# CDH-v4_11-A-DS1338-tcc-test-redesign.net
KiCad netlist of a schematic drawn in EAGLE
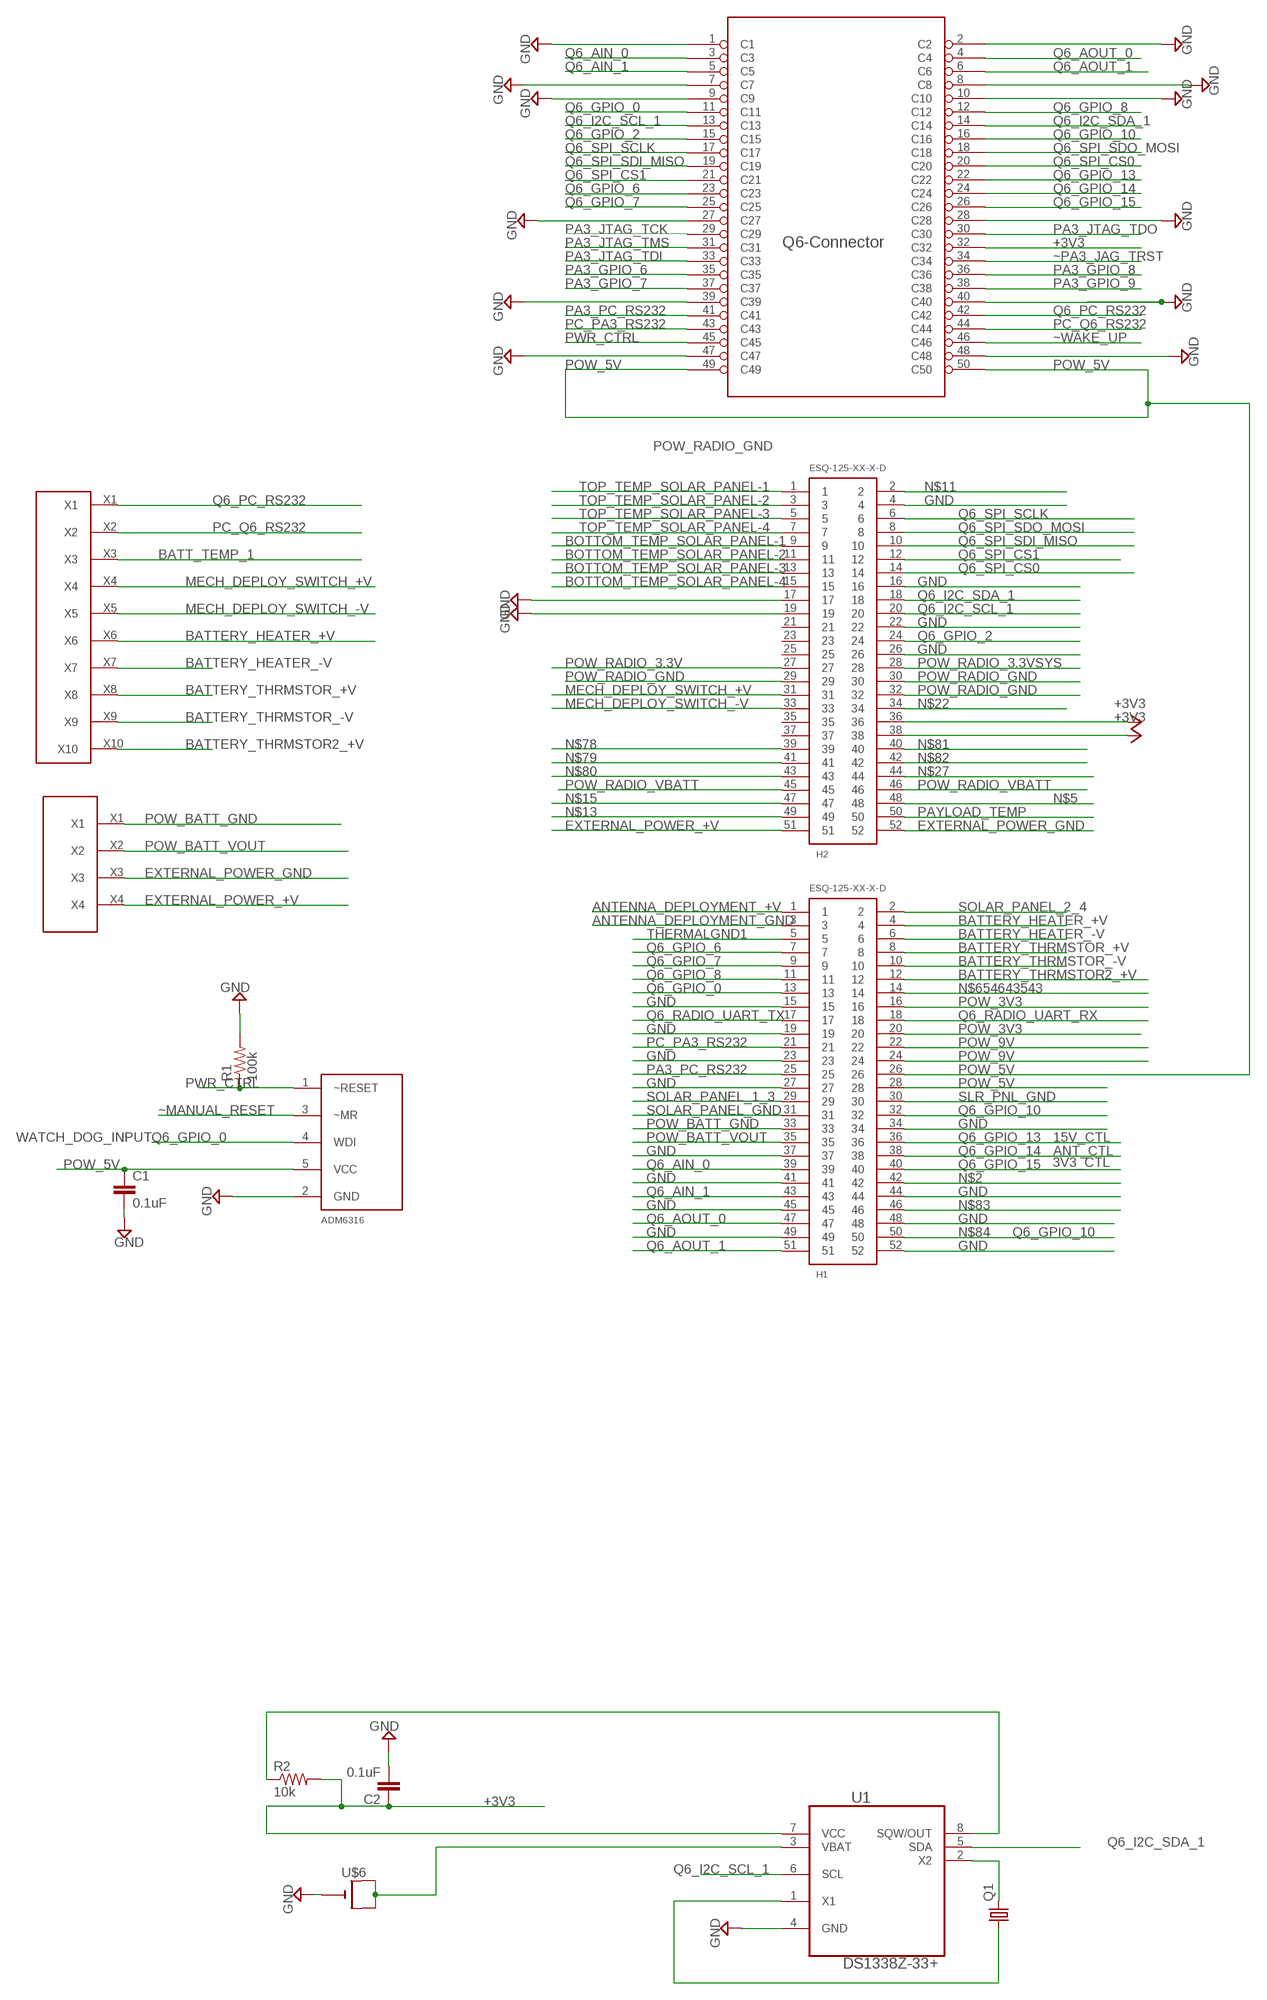
[diagram p0: schematic, sheet 1, part 1 of 2]
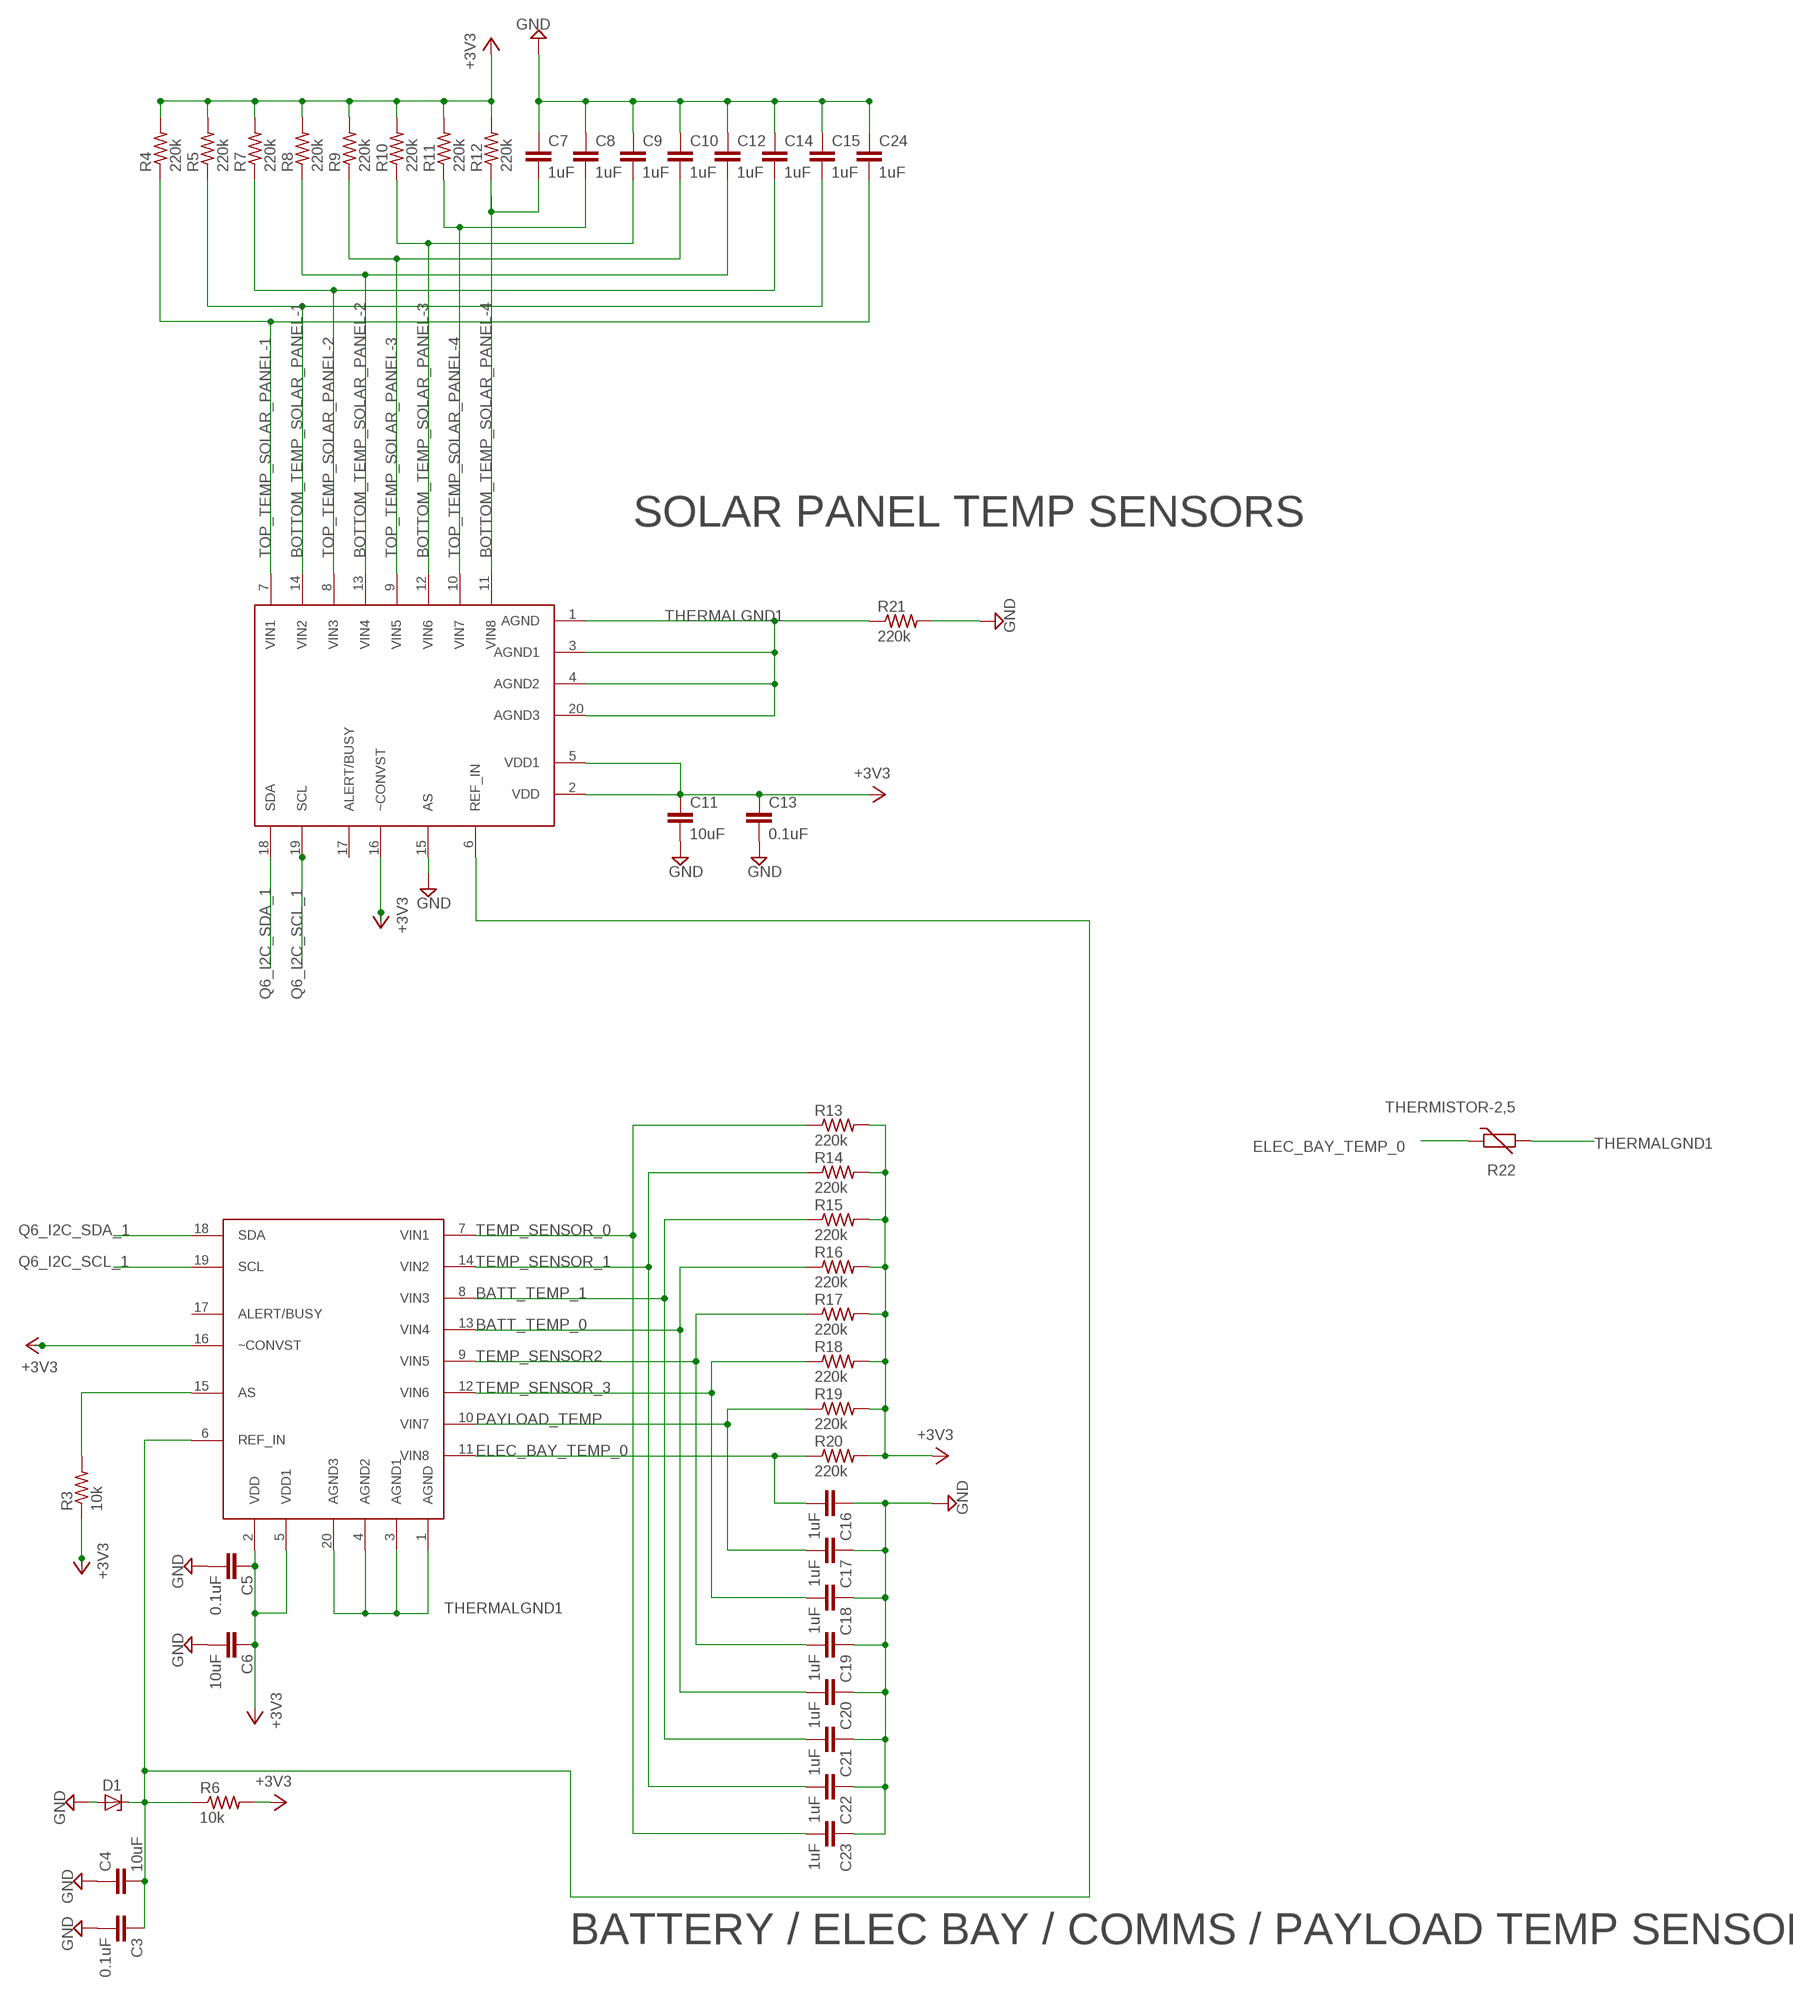
[diagram p1: schematic, sheet 1, part 2 of 2]

(export (version "E")
  (design (tool "Eeschema 10.0.6"))
  (components
    (comp (ref "ADC_TEMP_1")
      (value "AD7998-1")
      (footprint "eagle-import:TSSOP20")
      (libsource (lib "eagle-import") (part "AD7998-1"))
    )
    (comp (ref "ADC_TEMP_2")
      (value "AD7998-1")
      (footprint "eagle-import:TSSOP20")
      (libsource (lib "eagle-import") (part "AD7998-1"))
    )
    (comp (ref "C1")
      (value "0.1uF")
      (footprint "eagle-import:C2012")
      (libsource (lib "eagle-import") (part "C-EUC2012"))
    )
    (comp (ref "C2")
      (value "0.1uF")
      (footprint "eagle-import:C2012")
      (libsource (lib "eagle-import") (part "C-EUC2012"))
    )
    (comp (ref "C3")
      (value "0.1uF")
      (footprint "eagle-import:C2012")
      (libsource (lib "eagle-import") (part "C-EUC2012"))
    )
    (comp (ref "C4")
      (value "10uF")
      (footprint "eagle-import:C2012")
      (libsource (lib "eagle-import") (part "C-EUC2012"))
    )
    (comp (ref "C5")
      (value "0.1uF")
      (footprint "eagle-import:C2012")
      (libsource (lib "eagle-import") (part "C-EUC2012"))
    )
    (comp (ref "C6")
      (value "10uF")
      (footprint "eagle-import:C2012")
      (libsource (lib "eagle-import") (part "C-EUC2012"))
    )
    (comp (ref "C7")
      (value "1uF")
      (footprint "eagle-import:C2012")
      (libsource (lib "eagle-import") (part "C-EUC2012"))
    )
    (comp (ref "C8")
      (value "1uF")
      (footprint "eagle-import:C2012")
      (libsource (lib "eagle-import") (part "C-EUC2012"))
    )
    (comp (ref "C9")
      (value "1uF")
      (footprint "eagle-import:C2012")
      (libsource (lib "eagle-import") (part "C-EUC2012"))
    )
    (comp (ref "C10")
      (value "1uF")
      (footprint "eagle-import:C2012")
      (libsource (lib "eagle-import") (part "C-EUC2012"))
    )
    (comp (ref "C11")
      (value "10uF")
      (footprint "eagle-import:C2012")
      (libsource (lib "eagle-import") (part "C-EUC2012"))
    )
    (comp (ref "C12")
      (value "1uF")
      (footprint "eagle-import:C2012")
      (libsource (lib "eagle-import") (part "C-EUC2012"))
    )
    (comp (ref "C13")
      (value "0.1uF")
      (footprint "eagle-import:C2012")
      (libsource (lib "eagle-import") (part "C-EUC2012"))
    )
    (comp (ref "C14")
      (value "1uF")
      (footprint "eagle-import:C2012")
      (libsource (lib "eagle-import") (part "C-EUC2012"))
    )
    (comp (ref "C15")
      (value "1uF")
      (footprint "eagle-import:C2012")
      (libsource (lib "eagle-import") (part "C-EUC2012"))
    )
    (comp (ref "C16")
      (value "1uF")
      (footprint "eagle-import:C2012")
      (libsource (lib "eagle-import") (part "C-EUC2012"))
    )
    (comp (ref "C17")
      (value "1uF")
      (footprint "eagle-import:C2012")
      (libsource (lib "eagle-import") (part "C-EUC2012"))
    )
    (comp (ref "C18")
      (value "1uF")
      (footprint "eagle-import:C2012")
      (libsource (lib "eagle-import") (part "C-EUC2012"))
    )
    (comp (ref "C19")
      (value "1uF")
      (footprint "eagle-import:C2012")
      (libsource (lib "eagle-import") (part "C-EUC2012"))
    )
    (comp (ref "C20")
      (value "1uF")
      (footprint "eagle-import:C2012")
      (libsource (lib "eagle-import") (part "C-EUC2012"))
    )
    (comp (ref "C21")
      (value "1uF")
      (footprint "eagle-import:C2012")
      (libsource (lib "eagle-import") (part "C-EUC2012"))
    )
    (comp (ref "C22")
      (value "1uF")
      (footprint "eagle-import:C2012")
      (libsource (lib "eagle-import") (part "C-EUC2012"))
    )
    (comp (ref "C23")
      (value "1uF")
      (footprint "eagle-import:C2012")
      (libsource (lib "eagle-import") (part "C-EUC2012"))
    )
    (comp (ref "C24")
      (value "1uF")
      (footprint "eagle-import:C2012")
      (libsource (lib "eagle-import") (part "C-EUC2012"))
    )
    (comp (ref "D1")
      (value "ZENER-DIODESOD80C")
      (footprint "eagle-import:SOD80C")
      (libsource (lib "eagle-import") (part "ZENER-DIODESOD80C"))
    )
    (comp (ref "H1")
      (value "ESQ-125-XX-X-D")
      (footprint "eagle-import:ESQ-125-XX-X-D")
      (libsource (lib "eagle-import") (part "ESQ-125-XX-X-D"))
    )
    (comp (ref "H2")
      (value "ESQ-125-XX-X-D")
      (footprint "eagle-import:ESQ-125-XX-X-D")
      (libsource (lib "eagle-import") (part "ESQ-125-XX-X-D"))
    )
    (comp (ref "Q1")
      (value "CRYSTALTC38H")
      (footprint "eagle-import:TC38H")
      (libsource (lib "eagle-import") (part "CRYSTALTC38H"))
    )
    (comp (ref "R1")
      (value "100k")
      (footprint "eagle-import:R2012")
      (libsource (lib "eagle-import") (part "R-US_R2012"))
    )
    (comp (ref "R2")
      (value "10k")
      (footprint "eagle-import:R2012")
      (libsource (lib "eagle-import") (part "R-US_R2012"))
    )
    (comp (ref "R3")
      (value "10k")
      (footprint "eagle-import:R2012")
      (libsource (lib "eagle-import") (part "R-US_R2012"))
    )
    (comp (ref "R4")
      (value "220k")
      (footprint "eagle-import:R2012")
      (libsource (lib "eagle-import") (part "R-US_R2012"))
    )
    (comp (ref "R5")
      (value "220k")
      (footprint "eagle-import:R2012")
      (libsource (lib "eagle-import") (part "R-US_R2012"))
    )
    (comp (ref "R6")
      (value "10k")
      (footprint "eagle-import:R2012")
      (libsource (lib "eagle-import") (part "R-US_R2012"))
    )
    (comp (ref "R7")
      (value "220k")
      (footprint "eagle-import:R2012")
      (libsource (lib "eagle-import") (part "R-US_R2012"))
    )
    (comp (ref "R8")
      (value "220k")
      (footprint "eagle-import:R2012")
      (libsource (lib "eagle-import") (part "R-US_R2012"))
    )
    (comp (ref "R9")
      (value "220k")
      (footprint "eagle-import:R2012")
      (libsource (lib "eagle-import") (part "R-US_R2012"))
    )
    (comp (ref "R10")
      (value "220k")
      (footprint "eagle-import:R2012")
      (libsource (lib "eagle-import") (part "R-US_R2012"))
    )
    (comp (ref "R11")
      (value "220k")
      (footprint "eagle-import:R2012")
      (libsource (lib "eagle-import") (part "R-US_R2012"))
    )
    (comp (ref "R12")
      (value "220k")
      (footprint "eagle-import:R2012")
      (libsource (lib "eagle-import") (part "R-US_R2012"))
    )
    (comp (ref "R13")
      (value "220k")
      (footprint "eagle-import:R2012")
      (libsource (lib "eagle-import") (part "R-US_R2012"))
    )
    (comp (ref "R14")
      (value "220k")
      (footprint "eagle-import:R2012")
      (libsource (lib "eagle-import") (part "R-US_R2012"))
    )
    (comp (ref "R15")
      (value "220k")
      (footprint "eagle-import:R2012")
      (libsource (lib "eagle-import") (part "R-US_R2012"))
    )
    (comp (ref "R16")
      (value "220k")
      (footprint "eagle-import:R2012")
      (libsource (lib "eagle-import") (part "R-US_R2012"))
    )
    (comp (ref "R17")
      (value "220k")
      (footprint "eagle-import:R2012")
      (libsource (lib "eagle-import") (part "R-US_R2012"))
    )
    (comp (ref "R18")
      (value "220k")
      (footprint "eagle-import:R2012")
      (libsource (lib "eagle-import") (part "R-US_R2012"))
    )
    (comp (ref "R19")
      (value "220k")
      (footprint "eagle-import:R2012")
      (libsource (lib "eagle-import") (part "R-US_R2012"))
    )
    (comp (ref "R20")
      (value "220k")
      (footprint "eagle-import:R2012")
      (libsource (lib "eagle-import") (part "R-US_R2012"))
    )
    (comp (ref "R21")
      (value "220k")
      (footprint "eagle-import:R2012")
      (libsource (lib "eagle-import") (part "R-US_R2012"))
    )
    (comp (ref "R22")
      (value "THERMISTOR-2,5")
      (footprint "eagle-import:RS-2,5")
      (libsource (lib "eagle-import") (part "THERMISTOR-2,5"))
    )
    (comp (ref "U$1")
      (value "M80-5000000M1-10-331-00-000")
      (footprint "eagle-import:M80-5000000M1-04-331-00-000")
      (libsource (lib "eagle-import") (part "M80-5000000M1-10-331-00-000"))
    )
    (comp (ref "U$2")
      (value "M80-5000000M1-10-331-000")
      (footprint "eagle-import:M80-5000000M1")
      (libsource (lib "eagle-import") (part "M80-5000000M1-10-331-000"))
    )
    (comp (ref "U$3")
      (value "ADM6316/ADM6320")
      (footprint "eagle-import:SOT23-5")
      (libsource (lib "eagle-import") (part "ADM6316/ADM6320"))
    )
    (comp (ref "U$4")
      (value "SMFC")
      (footprint "eagle-import:SFMC-107-01-XX-D")
      (libsource (lib "eagle-import") (part "SMFC"))
    )
    (comp (ref "U$6")
      (value "CR1220SMT")
      (footprint "eagle-import:CR1220-SMD")
      (libsource (lib "eagle-import") (part "CR1220SMT"))
    )
    (comp (ref "U1")
      (value "DS1338Z-33+")
      (footprint "eagle-import:SOIC127P600X175-8N")
      (libsource (lib "eagle-import") (part "DS1338Z-33+"))
    )
  )
  (nets
    (net (code "1") (name "+3V3") (class "Default")
      (node (ref "ADC_TEMP_1") (pin "16") (pinfunction "~{CONVST}_16") (pintype "bidirectional"))
      (node (ref "ADC_TEMP_1") (pin "2") (pinfunction "VDD_2") (pintype "bidirectional"))
      (node (ref "ADC_TEMP_1") (pin "5") (pinfunction "VDD1_5") (pintype "bidirectional"))
      (node (ref "ADC_TEMP_2") (pin "16") (pinfunction "~{CONVST}_16") (pintype "bidirectional"))
      (node (ref "ADC_TEMP_2") (pin "2") (pinfunction "VDD_2") (pintype "bidirectional"))
      (node (ref "ADC_TEMP_2") (pin "5") (pinfunction "VDD1_5") (pintype "bidirectional"))
      (node (ref "C11") (pin "1") (pinfunction "1_1") (pintype "passive"))
      (node (ref "C13") (pin "1") (pinfunction "1_1") (pintype "passive"))
      (node (ref "C2") (pin "1") (pinfunction "1_1") (pintype "passive"))
      (node (ref "C5") (pin "1") (pinfunction "1_1") (pintype "passive"))
      (node (ref "C6") (pin "1") (pinfunction "1_1") (pintype "passive"))
      (node (ref "H2") (pin "36") (pinfunction "36_36") (pintype "bidirectional"))
      (node (ref "H2") (pin "38") (pinfunction "38_38") (pintype "bidirectional"))
      (node (ref "R10") (pin "2") (pinfunction "2_2") (pintype "passive"))
      (node (ref "R11") (pin "2") (pinfunction "2_2") (pintype "passive"))
      (node (ref "R12") (pin "2") (pinfunction "2_2") (pintype "passive"))
      (node (ref "R13") (pin "2") (pinfunction "2_2") (pintype "passive"))
      (node (ref "R14") (pin "2") (pinfunction "2_2") (pintype "passive"))
      (node (ref "R15") (pin "2") (pinfunction "2_2") (pintype "passive"))
      (node (ref "R16") (pin "2") (pinfunction "2_2") (pintype "passive"))
      (node (ref "R17") (pin "2") (pinfunction "2_2") (pintype "passive"))
      (node (ref "R18") (pin "2") (pinfunction "2_2") (pintype "passive"))
      (node (ref "R19") (pin "2") (pinfunction "2_2") (pintype "passive"))
      (node (ref "R2") (pin "2") (pinfunction "2_2") (pintype "passive"))
      (node (ref "R20") (pin "2") (pinfunction "2_2") (pintype "passive"))
      (node (ref "R3") (pin "1") (pinfunction "1_1") (pintype "passive"))
      (node (ref "R4") (pin "2") (pinfunction "2_2") (pintype "passive"))
      (node (ref "R5") (pin "2") (pinfunction "2_2") (pintype "passive"))
      (node (ref "R6") (pin "2") (pinfunction "2_2") (pintype "passive"))
      (node (ref "R7") (pin "2") (pinfunction "2_2") (pintype "passive"))
      (node (ref "R8") (pin "2") (pinfunction "2_2") (pintype "passive"))
      (node (ref "R9") (pin "2") (pinfunction "2_2") (pintype "passive"))
      (node (ref "U$4") (pin "32") (pinfunction "C32_32") (pintype "bidirectional"))
      (node (ref "U1") (pin "7") (pinfunction "VCC_7") (pintype "power_in"))
    )
    (net (code "2") (name "/ANTENNA_DEPLOYMENT_+V") (class "Default")
      (node (ref "H1") (pin "1") (pinfunction "1_1") (pintype "bidirectional"))
    )
    (net (code "3") (name "/ANTENNA_DEPLOYMENT_GND") (class "Default")
      (node (ref "H1") (pin "3") (pinfunction "3_3") (pintype "bidirectional"))
    )
    (net (code "4") (name "/BATTERY_HEATER_+V") (class "Default")
      (node (ref "H1") (pin "4") (pinfunction "4_4") (pintype "bidirectional"))
      (node (ref "U$2") (pin "X6") (pinfunction "X6_X6") (pintype "bidirectional"))
    )
    (net (code "5") (name "/BATTERY_HEATER_-V") (class "Default")
      (node (ref "H1") (pin "6") (pinfunction "6_6") (pintype "bidirectional"))
      (node (ref "U$2") (pin "X7") (pinfunction "X7_X7") (pintype "bidirectional"))
    )
    (net (code "6") (name "/BATTERY_THRMSTOR2_+V") (class "Default")
      (node (ref "H1") (pin "12") (pinfunction "12_12") (pintype "bidirectional"))
      (node (ref "U$2") (pin "X10") (pinfunction "X10_X10") (pintype "bidirectional"))
    )
    (net (code "7") (name "/BATTERY_THRMSTOR_+V") (class "Default")
      (node (ref "H1") (pin "8") (pinfunction "8_8") (pintype "bidirectional"))
      (node (ref "U$2") (pin "X8") (pinfunction "X8_X8") (pintype "bidirectional"))
    )
    (net (code "8") (name "/BATTERY_THRMSTOR_-V") (class "Default")
      (node (ref "H1") (pin "10") (pinfunction "10_10") (pintype "bidirectional"))
      (node (ref "U$2") (pin "X9") (pinfunction "X9_X9") (pintype "bidirectional"))
    )
    (net (code "9") (name "/BATT_TEMP_0") (class "Default")
      (node (ref "ADC_TEMP_1") (pin "13") (pinfunction "VIN4_13") (pintype "bidirectional"))
      (node (ref "C20") (pin "2") (pinfunction "2_2") (pintype "passive"))
      (node (ref "R16") (pin "1") (pinfunction "1_1") (pintype "passive"))
    )
    (net (code "10") (name "/BATT_TEMP_1") (class "Default")
      (node (ref "ADC_TEMP_1") (pin "8") (pinfunction "VIN3_8") (pintype "bidirectional"))
      (node (ref "C21") (pin "2") (pinfunction "2_2") (pintype "passive"))
      (node (ref "R15") (pin "1") (pinfunction "1_1") (pintype "passive"))
      (node (ref "U$2") (pin "X3") (pinfunction "X3_X3") (pintype "bidirectional"))
    )
    (net (code "11") (name "/BOTTOM_TEMP_SOLAR_PANEL-1") (class "Default")
      (node (ref "ADC_TEMP_2") (pin "14") (pinfunction "VIN2_14") (pintype "bidirectional"))
      (node (ref "C15") (pin "2") (pinfunction "2_2") (pintype "passive"))
      (node (ref "H2") (pin "9") (pinfunction "9_9") (pintype "bidirectional"))
      (node (ref "R5") (pin "1") (pinfunction "1_1") (pintype "passive"))
    )
    (net (code "12") (name "/BOTTOM_TEMP_SOLAR_PANEL-2") (class "Default")
      (node (ref "ADC_TEMP_2") (pin "13") (pinfunction "VIN4_13") (pintype "bidirectional"))
      (node (ref "C12") (pin "2") (pinfunction "2_2") (pintype "passive"))
      (node (ref "H2") (pin "11") (pinfunction "11_11") (pintype "bidirectional"))
      (node (ref "R8") (pin "1") (pinfunction "1_1") (pintype "passive"))
    )
    (net (code "13") (name "/BOTTOM_TEMP_SOLAR_PANEL-3") (class "Default")
      (node (ref "ADC_TEMP_2") (pin "12") (pinfunction "VIN6_12") (pintype "bidirectional"))
      (node (ref "C9") (pin "2") (pinfunction "2_2") (pintype "passive"))
      (node (ref "H2") (pin "13") (pinfunction "13_13") (pintype "bidirectional"))
      (node (ref "R10") (pin "1") (pinfunction "1_1") (pintype "passive"))
    )
    (net (code "14") (name "/BOTTOM_TEMP_SOLAR_PANEL-4") (class "Default")
      (node (ref "ADC_TEMP_2") (pin "11") (pinfunction "VIN8_11") (pintype "bidirectional"))
      (node (ref "C7") (pin "2") (pinfunction "2_2") (pintype "passive"))
      (node (ref "H2") (pin "15") (pinfunction "15_15") (pintype "bidirectional"))
      (node (ref "R12") (pin "1") (pinfunction "1_1") (pintype "passive"))
    )
    (net (code "15") (name "/ELEC_BAY_TEMP_0") (class "Default")
      (node (ref "ADC_TEMP_1") (pin "11") (pinfunction "VIN8_11") (pintype "bidirectional"))
      (node (ref "C16") (pin "2") (pinfunction "2_2") (pintype "passive"))
      (node (ref "R20") (pin "1") (pinfunction "1_1") (pintype "passive"))
      (node (ref "R22") (pin "1") (pinfunction "1_1") (pintype "passive"))
    )
    (net (code "16") (name "/EXTERNAL_POWER_+V") (class "Default")
      (node (ref "H2") (pin "51") (pinfunction "51_51") (pintype "bidirectional"))
      (node (ref "U$1") (pin "X4") (pinfunction "X4_X4") (pintype "bidirectional"))
    )
    (net (code "17") (name "/EXTERNAL_POWER_GND") (class "Default")
      (node (ref "H2") (pin "52") (pinfunction "52_52") (pintype "bidirectional"))
      (node (ref "U$1") (pin "X3") (pinfunction "X3_X3") (pintype "bidirectional"))
    )
    (net (code "18") (name "/MECH_DEPLOY_SWITCH_+V") (class "Default")
      (node (ref "H2") (pin "31") (pinfunction "31_31") (pintype "bidirectional"))
      (node (ref "U$2") (pin "X4") (pinfunction "X4_X4") (pintype "bidirectional"))
    )
    (net (code "19") (name "/MECH_DEPLOY_SWITCH_-V") (class "Default")
      (node (ref "H2") (pin "33") (pinfunction "33_33") (pintype "bidirectional"))
      (node (ref "U$2") (pin "X5") (pinfunction "X5_X5") (pintype "bidirectional"))
    )
    (net (code "20") (name "/N$2") (class "Default")
      (node (ref "H1") (pin "42") (pinfunction "42_42") (pintype "bidirectional"))
    )
    (net (code "21") (name "/N$5") (class "Default")
      (node (ref "H2") (pin "48") (pinfunction "48_48") (pintype "bidirectional"))
    )
    (net (code "22") (name "/N$11") (class "Default")
      (node (ref "H2") (pin "2") (pinfunction "2_2") (pintype "bidirectional"))
    )
    (net (code "23") (name "/N$13") (class "Default")
      (node (ref "H2") (pin "49") (pinfunction "49_49") (pintype "bidirectional"))
    )
    (net (code "24") (name "/N$15") (class "Default")
      (node (ref "H2") (pin "47") (pinfunction "47_47") (pintype "bidirectional"))
    )
    (net (code "25") (name "/N$22") (class "Default")
      (node (ref "H2") (pin "34") (pinfunction "34_34") (pintype "bidirectional"))
    )
    (net (code "26") (name "/N$27") (class "Default")
      (node (ref "H2") (pin "44") (pinfunction "44_44") (pintype "bidirectional"))
    )
    (net (code "27") (name "/N$78") (class "Default")
      (node (ref "H2") (pin "39") (pinfunction "39_39") (pintype "bidirectional"))
    )
    (net (code "28") (name "/N$79") (class "Default")
      (node (ref "H2") (pin "41") (pinfunction "41_41") (pintype "bidirectional"))
    )
    (net (code "29") (name "/N$80") (class "Default")
      (node (ref "H2") (pin "43") (pinfunction "43_43") (pintype "bidirectional"))
    )
    (net (code "30") (name "/N$81") (class "Default")
      (node (ref "H2") (pin "40") (pinfunction "40_40") (pintype "bidirectional"))
    )
    (net (code "31") (name "/N$82") (class "Default")
      (node (ref "H2") (pin "42") (pinfunction "42_42") (pintype "bidirectional"))
    )
    (net (code "32") (name "/N$83") (class "Default")
      (node (ref "H1") (pin "46") (pinfunction "46_46") (pintype "bidirectional"))
    )
    (net (code "33") (name "/N$84") (class "Default")
      (node (ref "H1") (pin "50") (pinfunction "50_50") (pintype "bidirectional"))
    )
    (net (code "34") (name "/N$654643543") (class "Default")
      (node (ref "H1") (pin "14") (pinfunction "14_14") (pintype "bidirectional"))
    )
    (net (code "35") (name "/PA3_GPIO_6") (class "Default")
      (node (ref "U$4") (pin "35") (pinfunction "C35_35") (pintype "bidirectional"))
    )
    (net (code "36") (name "/PA3_GPIO_7") (class "Default")
      (node (ref "U$4") (pin "37") (pinfunction "C37_37") (pintype "bidirectional"))
    )
    (net (code "37") (name "/PA3_GPIO_8") (class "Default")
      (node (ref "U$4") (pin "36") (pinfunction "C36_36") (pintype "bidirectional"))
    )
    (net (code "38") (name "/PA3_GPIO_9") (class "Default")
      (node (ref "U$4") (pin "38") (pinfunction "C38_38") (pintype "bidirectional"))
    )
    (net (code "39") (name "/PA3_JTAG_TCK") (class "Default")
      (node (ref "U$4") (pin "29") (pinfunction "C29_29") (pintype "bidirectional"))
    )
    (net (code "40") (name "/PA3_JTAG_TDI") (class "Default")
      (node (ref "U$4") (pin "33") (pinfunction "C33_33") (pintype "bidirectional"))
    )
    (net (code "41") (name "/PA3_JTAG_TDO") (class "Default")
      (node (ref "U$4") (pin "30") (pinfunction "C30_30") (pintype "bidirectional"))
    )
    (net (code "42") (name "/PA3_JTAG_TMS") (class "Default")
      (node (ref "U$4") (pin "31") (pinfunction "C31_31") (pintype "bidirectional"))
    )
    (net (code "43") (name "/PA3_PC_RS232") (class "Default")
      (node (ref "H1") (pin "25") (pinfunction "25_25") (pintype "bidirectional"))
      (node (ref "U$4") (pin "41") (pinfunction "C41_41") (pintype "bidirectional"))
    )
    (net (code "44") (name "/PAYLOAD_TEMP") (class "Default")
      (node (ref "ADC_TEMP_1") (pin "10") (pinfunction "VIN7_10") (pintype "bidirectional"))
      (node (ref "C17") (pin "2") (pinfunction "2_2") (pintype "passive"))
      (node (ref "H2") (pin "50") (pinfunction "50_50") (pintype "bidirectional"))
      (node (ref "R19") (pin "1") (pinfunction "1_1") (pintype "passive"))
    )
    (net (code "45") (name "/PC_PA3_RS232") (class "Default")
      (node (ref "H1") (pin "21") (pinfunction "21_21") (pintype "bidirectional"))
      (node (ref "U$4") (pin "43") (pinfunction "C43_43") (pintype "bidirectional"))
    )
    (net (code "46") (name "/PC_Q6_RS232") (class "Default")
      (node (ref "U$2") (pin "X2") (pinfunction "X2_X2") (pintype "bidirectional"))
      (node (ref "U$4") (pin "44") (pinfunction "C44_44") (pintype "bidirectional"))
    )
    (net (code "47") (name "/POW_3V3") (class "Default")
      (node (ref "H1") (pin "16") (pinfunction "16_16") (pintype "bidirectional"))
      (node (ref "H1") (pin "20") (pinfunction "20_20") (pintype "bidirectional"))
    )
    (net (code "48") (name "/POW_5V") (class "Default")
      (node (ref "C1") (pin "1") (pinfunction "1_1") (pintype "passive"))
      (node (ref "H1") (pin "26") (pinfunction "26_26") (pintype "bidirectional"))
      (node (ref "H1") (pin "28") (pinfunction "28_28") (pintype "bidirectional"))
      (node (ref "U$3") (pin "5") (pinfunction "VCC_5") (pintype "bidirectional"))
      (node (ref "U$4") (pin "49") (pinfunction "C49_49") (pintype "bidirectional"))
      (node (ref "U$4") (pin "50") (pinfunction "C50_50") (pintype "bidirectional"))
    )
    (net (code "49") (name "/POW_9V") (class "Default")
      (node (ref "H1") (pin "22") (pinfunction "22_22") (pintype "bidirectional"))
      (node (ref "H1") (pin "24") (pinfunction "24_24") (pintype "bidirectional"))
    )
    (net (code "50") (name "/POW_BATT_GND") (class "Default")
      (node (ref "H1") (pin "33") (pinfunction "33_33") (pintype "bidirectional"))
      (node (ref "U$1") (pin "X1") (pinfunction "X1_X1") (pintype "bidirectional"))
    )
    (net (code "51") (name "/POW_BATT_VOUT") (class "Default")
      (node (ref "H1") (pin "35") (pinfunction "35_35") (pintype "bidirectional"))
      (node (ref "U$1") (pin "X2") (pinfunction "X2_X2") (pintype "bidirectional"))
    )
    (net (code "52") (name "/POW_RADIO_3.3V") (class "Default")
      (node (ref "H2") (pin "27") (pinfunction "27_27") (pintype "bidirectional"))
    )
    (net (code "53") (name "/POW_RADIO_3.3VSYS") (class "Default")
      (node (ref "H2") (pin "28") (pinfunction "28_28") (pintype "bidirectional"))
    )
    (net (code "54") (name "/POW_RADIO_GND") (class "Default")
      (node (ref "H2") (pin "29") (pinfunction "29_29") (pintype "bidirectional"))
      (node (ref "H2") (pin "30") (pinfunction "30_30") (pintype "bidirectional"))
      (node (ref "H2") (pin "32") (pinfunction "32_32") (pintype "bidirectional"))
    )
    (net (code "55") (name "/POW_RADIO_VBATT") (class "Default")
      (node (ref "H2") (pin "45") (pinfunction "45_45") (pintype "bidirectional"))
      (node (ref "H2") (pin "46") (pinfunction "46_46") (pintype "bidirectional"))
    )
    (net (code "56") (name "/PWR_CTRL") (class "Default")
      (node (ref "R1") (pin "1") (pinfunction "1_1") (pintype "passive"))
      (node (ref "U$3") (pin "1") (pinfunction "~{RESET}_1") (pintype "bidirectional"))
      (node (ref "U$4") (pin "45") (pinfunction "C45_45") (pintype "bidirectional"))
    )
    (net (code "57") (name "/Q6_AIN_0") (class "Default")
      (node (ref "H1") (pin "39") (pinfunction "39_39") (pintype "bidirectional"))
      (node (ref "U$4") (pin "3") (pinfunction "C3_3") (pintype "bidirectional"))
    )
    (net (code "58") (name "/Q6_AIN_1") (class "Default")
      (node (ref "H1") (pin "43") (pinfunction "43_43") (pintype "bidirectional"))
      (node (ref "U$4") (pin "5") (pinfunction "C5_5") (pintype "bidirectional"))
    )
    (net (code "59") (name "/Q6_AOUT_0") (class "Default")
      (node (ref "H1") (pin "47") (pinfunction "47_47") (pintype "bidirectional"))
      (node (ref "U$4") (pin "4") (pinfunction "C4_4") (pintype "bidirectional"))
    )
    (net (code "60") (name "/Q6_AOUT_1") (class "Default")
      (node (ref "H1") (pin "51") (pinfunction "51_51") (pintype "bidirectional"))
      (node (ref "U$4") (pin "6") (pinfunction "C6_6") (pintype "bidirectional"))
    )
    (net (code "61") (name "/Q6_GPIO_0") (class "Default")
      (node (ref "H1") (pin "13") (pinfunction "13_13") (pintype "bidirectional"))
      (node (ref "U$3") (pin "4") (pinfunction "WDI_4") (pintype "bidirectional"))
      (node (ref "U$4") (pin "11") (pinfunction "C11_11") (pintype "bidirectional"))
    )
    (net (code "62") (name "/Q6_GPIO_2") (class "Default")
      (node (ref "H2") (pin "24") (pinfunction "24_24") (pintype "bidirectional"))
      (node (ref "U$4") (pin "15") (pinfunction "C15_15") (pintype "bidirectional"))
    )
    (net (code "63") (name "/Q6_GPIO_6") (class "Default")
      (node (ref "H1") (pin "7") (pinfunction "7_7") (pintype "bidirectional"))
      (node (ref "U$4") (pin "23") (pinfunction "C23_23") (pintype "bidirectional"))
    )
    (net (code "64") (name "/Q6_GPIO_7") (class "Default")
      (node (ref "H1") (pin "9") (pinfunction "9_9") (pintype "bidirectional"))
      (node (ref "U$4") (pin "25") (pinfunction "C25_25") (pintype "bidirectional"))
    )
    (net (code "65") (name "/Q6_GPIO_8") (class "Default")
      (node (ref "H1") (pin "11") (pinfunction "11_11") (pintype "bidirectional"))
      (node (ref "U$4") (pin "12") (pinfunction "C12_12") (pintype "bidirectional"))
    )
    (net (code "66") (name "/Q6_GPIO_10") (class "Default")
      (node (ref "H1") (pin "32") (pinfunction "32_32") (pintype "bidirectional"))
      (node (ref "U$4") (pin "16") (pinfunction "C16_16") (pintype "bidirectional"))
    )
    (net (code "67") (name "/Q6_GPIO_13") (class "Default")
      (node (ref "H1") (pin "36") (pinfunction "36_36") (pintype "bidirectional"))
      (node (ref "U$4") (pin "22") (pinfunction "C22_22") (pintype "bidirectional"))
    )
    (net (code "68") (name "/Q6_GPIO_14") (class "Default")
      (node (ref "H1") (pin "38") (pinfunction "38_38") (pintype "bidirectional"))
      (node (ref "U$4") (pin "24") (pinfunction "C24_24") (pintype "bidirectional"))
    )
    (net (code "69") (name "/Q6_GPIO_15") (class "Default")
      (node (ref "H1") (pin "40") (pinfunction "40_40") (pintype "bidirectional"))
      (node (ref "U$4") (pin "26") (pinfunction "C26_26") (pintype "bidirectional"))
    )
    (net (code "70") (name "/Q6_I2C_SCL_1") (class "Default")
      (node (ref "ADC_TEMP_1") (pin "19") (pinfunction "SCL_19") (pintype "bidirectional"))
      (node (ref "ADC_TEMP_2") (pin "19") (pinfunction "SCL_19") (pintype "bidirectional"))
      (node (ref "H2") (pin "20") (pinfunction "20_20") (pintype "bidirectional"))
      (node (ref "U$4") (pin "13") (pinfunction "C13_13") (pintype "bidirectional"))
      (node (ref "U1") (pin "6") (pinfunction "SCL_6") (pintype "input"))
    )
    (net (code "71") (name "/Q6_I2C_SDA_1") (class "Default")
      (node (ref "ADC_TEMP_1") (pin "18") (pinfunction "SDA_18") (pintype "bidirectional"))
      (node (ref "ADC_TEMP_2") (pin "18") (pinfunction "SDA_18") (pintype "bidirectional"))
      (node (ref "H2") (pin "18") (pinfunction "18_18") (pintype "bidirectional"))
      (node (ref "U$4") (pin "14") (pinfunction "C14_14") (pintype "bidirectional"))
      (node (ref "U1") (pin "5") (pinfunction "SDA_5") (pintype "bidirectional"))
    )
    (net (code "72") (name "/Q6_PC_RS232") (class "Default")
      (node (ref "U$2") (pin "X1") (pinfunction "X1_X1") (pintype "bidirectional"))
      (node (ref "U$4") (pin "42") (pinfunction "C42_42") (pintype "bidirectional"))
    )
    (net (code "73") (name "/Q6_RADIO_UART_RX") (class "Default")
      (node (ref "H1") (pin "18") (pinfunction "18_18") (pintype "bidirectional"))
    )
    (net (code "74") (name "/Q6_RADIO_UART_TX") (class "Default")
      (node (ref "H1") (pin "17") (pinfunction "17_17") (pintype "bidirectional"))
    )
    (net (code "75") (name "/Q6_SPI_CS0") (class "Default")
      (node (ref "H2") (pin "14") (pinfunction "14_14") (pintype "bidirectional"))
      (node (ref "U$4") (pin "20") (pinfunction "C20_20") (pintype "bidirectional"))
    )
    (net (code "76") (name "/Q6_SPI_CS1") (class "Default")
      (node (ref "H2") (pin "12") (pinfunction "12_12") (pintype "bidirectional"))
      (node (ref "U$4") (pin "21") (pinfunction "C21_21") (pintype "bidirectional"))
    )
    (net (code "77") (name "/Q6_SPI_SCLK") (class "Default")
      (node (ref "H2") (pin "6") (pinfunction "6_6") (pintype "bidirectional"))
      (node (ref "U$4") (pin "17") (pinfunction "C17_17") (pintype "bidirectional"))
    )
    (net (code "78") (name "/Q6_SPI_SDI_MISO") (class "Default")
      (node (ref "H2") (pin "10") (pinfunction "10_10") (pintype "bidirectional"))
      (node (ref "U$4") (pin "19") (pinfunction "C19_19") (pintype "bidirectional"))
    )
    (net (code "79") (name "/Q6_SPI_SDO_MOSI") (class "Default")
      (node (ref "H2") (pin "8") (pinfunction "8_8") (pintype "bidirectional"))
      (node (ref "U$4") (pin "18") (pinfunction "C18_18") (pintype "bidirectional"))
    )
    (net (code "80") (name "/SLR_PNL_GND") (class "Default")
      (node (ref "H1") (pin "30") (pinfunction "30_30") (pintype "bidirectional"))
    )
    (net (code "81") (name "/SOLAR_PANEL_1_3") (class "Default")
      (node (ref "H1") (pin "29") (pinfunction "29_29") (pintype "bidirectional"))
    )
    (net (code "82") (name "/SOLAR_PANEL_GND") (class "Default")
      (node (ref "H1") (pin "31") (pinfunction "31_31") (pintype "bidirectional"))
    )
    (net (code "83") (name "/TEMP_SENSOR2") (class "Default")
      (node (ref "ADC_TEMP_1") (pin "9") (pinfunction "VIN5_9") (pintype "bidirectional"))
      (node (ref "C19") (pin "2") (pinfunction "2_2") (pintype "passive"))
      (node (ref "R17") (pin "1") (pinfunction "1_1") (pintype "passive"))
    )
    (net (code "84") (name "/TEMP_SENSOR_0") (class "Default")
      (node (ref "ADC_TEMP_1") (pin "7") (pinfunction "VIN1_7") (pintype "bidirectional"))
      (node (ref "C23") (pin "2") (pinfunction "2_2") (pintype "passive"))
      (node (ref "R13") (pin "1") (pinfunction "1_1") (pintype "passive"))
    )
    (net (code "85") (name "/TEMP_SENSOR_1") (class "Default")
      (node (ref "ADC_TEMP_1") (pin "14") (pinfunction "VIN2_14") (pintype "bidirectional"))
      (node (ref "C22") (pin "2") (pinfunction "2_2") (pintype "passive"))
      (node (ref "R14") (pin "1") (pinfunction "1_1") (pintype "passive"))
    )
    (net (code "86") (name "/TEMP_SENSOR_3") (class "Default")
      (node (ref "ADC_TEMP_1") (pin "12") (pinfunction "VIN6_12") (pintype "bidirectional"))
      (node (ref "C18") (pin "2") (pinfunction "2_2") (pintype "passive"))
      (node (ref "R18") (pin "1") (pinfunction "1_1") (pintype "passive"))
    )
    (net (code "87") (name "/THERMALGND1") (class "Default")
      (node (ref "ADC_TEMP_1") (pin "1") (pinfunction "AGND_1") (pintype "bidirectional"))
      (node (ref "ADC_TEMP_1") (pin "20") (pinfunction "AGND3_20") (pintype "bidirectional"))
      (node (ref "ADC_TEMP_1") (pin "3") (pinfunction "AGND1_3") (pintype "bidirectional"))
      (node (ref "ADC_TEMP_1") (pin "4") (pinfunction "AGND2_4") (pintype "bidirectional"))
      (node (ref "ADC_TEMP_2") (pin "1") (pinfunction "AGND_1") (pintype "bidirectional"))
      (node (ref "ADC_TEMP_2") (pin "20") (pinfunction "AGND3_20") (pintype "bidirectional"))
      (node (ref "ADC_TEMP_2") (pin "3") (pinfunction "AGND1_3") (pintype "bidirectional"))
      (node (ref "ADC_TEMP_2") (pin "4") (pinfunction "AGND2_4") (pintype "bidirectional"))
      (node (ref "H1") (pin "5") (pinfunction "5_5") (pintype "bidirectional"))
      (node (ref "R21") (pin "1") (pinfunction "1_1") (pintype "passive"))
      (node (ref "R22") (pin "2") (pinfunction "2_2") (pintype "passive"))
    )
    (net (code "88") (name "/TOP_TEMP_SOLAR_PANEL-1") (class "Default")
      (node (ref "ADC_TEMP_2") (pin "7") (pinfunction "VIN1_7") (pintype "bidirectional"))
      (node (ref "C24") (pin "2") (pinfunction "2_2") (pintype "passive"))
      (node (ref "H2") (pin "1") (pinfunction "1_1") (pintype "bidirectional"))
      (node (ref "R4") (pin "1") (pinfunction "1_1") (pintype "passive"))
    )
    (net (code "89") (name "/TOP_TEMP_SOLAR_PANEL-2") (class "Default")
      (node (ref "ADC_TEMP_2") (pin "8") (pinfunction "VIN3_8") (pintype "bidirectional"))
      (node (ref "C14") (pin "2") (pinfunction "2_2") (pintype "passive"))
      (node (ref "H2") (pin "3") (pinfunction "3_3") (pintype "bidirectional"))
      (node (ref "R7") (pin "1") (pinfunction "1_1") (pintype "passive"))
    )
    (net (code "90") (name "/TOP_TEMP_SOLAR_PANEL-3") (class "Default")
      (node (ref "ADC_TEMP_2") (pin "9") (pinfunction "VIN5_9") (pintype "bidirectional"))
      (node (ref "C10") (pin "2") (pinfunction "2_2") (pintype "passive"))
      (node (ref "H2") (pin "5") (pinfunction "5_5") (pintype "bidirectional"))
      (node (ref "R9") (pin "1") (pinfunction "1_1") (pintype "passive"))
    )
    (net (code "91") (name "/TOP_TEMP_SOLAR_PANEL-4") (class "Default")
      (node (ref "ADC_TEMP_2") (pin "10") (pinfunction "VIN7_10") (pintype "bidirectional"))
      (node (ref "C8") (pin "2") (pinfunction "2_2") (pintype "passive"))
      (node (ref "H2") (pin "7") (pinfunction "7_7") (pintype "bidirectional"))
      (node (ref "R11") (pin "1") (pinfunction "1_1") (pintype "passive"))
    )
    (net (code "92") (name "/~{MANUAL_RESET}") (class "Default")
      (node (ref "U$3") (pin "3") (pinfunction "~{MR}_3") (pintype "bidirectional"))
    )
    (net (code "93") (name "/~{PA3_JAG_TRST}") (class "Default")
      (node (ref "U$4") (pin "34") (pinfunction "C34_34") (pintype "bidirectional"))
    )
    (net (code "94") (name "/~{WAKE_UP}") (class "Default")
      (node (ref "U$4") (pin "46") (pinfunction "C46_46") (pintype "bidirectional"))
    )
    (net (code "95") (name "GND") (class "Default")
      (node (ref "ADC_TEMP_2") (pin "15") (pinfunction "AS_15") (pintype "bidirectional"))
      (node (ref "C1") (pin "2") (pinfunction "2_2") (pintype "passive"))
      (node (ref "C10") (pin "1") (pinfunction "1_1") (pintype "passive"))
      (node (ref "C11") (pin "2") (pinfunction "2_2") (pintype "passive"))
      (node (ref "C12") (pin "1") (pinfunction "1_1") (pintype "passive"))
      (node (ref "C13") (pin "2") (pinfunction "2_2") (pintype "passive"))
      (node (ref "C14") (pin "1") (pinfunction "1_1") (pintype "passive"))
      (node (ref "C15") (pin "1") (pinfunction "1_1") (pintype "passive"))
      (node (ref "C16") (pin "1") (pinfunction "1_1") (pintype "passive"))
      (node (ref "C17") (pin "1") (pinfunction "1_1") (pintype "passive"))
      (node (ref "C18") (pin "1") (pinfunction "1_1") (pintype "passive"))
      (node (ref "C19") (pin "1") (pinfunction "1_1") (pintype "passive"))
      (node (ref "C2") (pin "2") (pinfunction "2_2") (pintype "passive"))
      (node (ref "C20") (pin "1") (pinfunction "1_1") (pintype "passive"))
      (node (ref "C21") (pin "1") (pinfunction "1_1") (pintype "passive"))
      (node (ref "C22") (pin "1") (pinfunction "1_1") (pintype "passive"))
      (node (ref "C23") (pin "1") (pinfunction "1_1") (pintype "passive"))
      (node (ref "C24") (pin "1") (pinfunction "1_1") (pintype "passive"))
      (node (ref "C3") (pin "2") (pinfunction "2_2") (pintype "passive"))
      (node (ref "C4") (pin "1") (pinfunction "1_1") (pintype "passive"))
      (node (ref "C5") (pin "2") (pinfunction "2_2") (pintype "passive"))
      (node (ref "C6") (pin "2") (pinfunction "2_2") (pintype "passive"))
      (node (ref "C7") (pin "1") (pinfunction "1_1") (pintype "passive"))
      (node (ref "C8") (pin "1") (pinfunction "1_1") (pintype "passive"))
      (node (ref "C9") (pin "1") (pinfunction "1_1") (pintype "passive"))
      (node (ref "D1") (pin "A") (pinfunction "A_A") (pintype "passive"))
      (node (ref "H1") (pin "15") (pinfunction "15_15") (pintype "bidirectional"))
      (node (ref "H1") (pin "19") (pinfunction "19_19") (pintype "bidirectional"))
      (node (ref "H1") (pin "23") (pinfunction "23_23") (pintype "bidirectional"))
      (node (ref "H1") (pin "27") (pinfunction "27_27") (pintype "bidirectional"))
      (node (ref "H1") (pin "34") (pinfunction "34_34") (pintype "bidirectional"))
      (node (ref "H1") (pin "37") (pinfunction "37_37") (pintype "bidirectional"))
      (node (ref "H1") (pin "41") (pinfunction "41_41") (pintype "bidirectional"))
      (node (ref "H1") (pin "44") (pinfunction "44_44") (pintype "bidirectional"))
      (node (ref "H1") (pin "45") (pinfunction "45_45") (pintype "bidirectional"))
      (node (ref "H1") (pin "48") (pinfunction "48_48") (pintype "bidirectional"))
      (node (ref "H1") (pin "49") (pinfunction "49_49") (pintype "bidirectional"))
      (node (ref "H1") (pin "52") (pinfunction "52_52") (pintype "bidirectional"))
      (node (ref "H2") (pin "16") (pinfunction "16_16") (pintype "bidirectional"))
      (node (ref "H2") (pin "17") (pinfunction "17_17") (pintype "bidirectional"))
      (node (ref "H2") (pin "19") (pinfunction "19_19") (pintype "bidirectional"))
      (node (ref "H2") (pin "22") (pinfunction "22_22") (pintype "bidirectional"))
      (node (ref "H2") (pin "26") (pinfunction "26_26") (pintype "bidirectional"))
      (node (ref "H2") (pin "4") (pinfunction "4_4") (pintype "bidirectional"))
      (node (ref "R1") (pin "2") (pinfunction "2_2") (pintype "passive"))
      (node (ref "R21") (pin "2") (pinfunction "2_2") (pintype "passive"))
      (node (ref "U$3") (pin "2") (pinfunction "GND_2") (pintype "bidirectional"))
      (node (ref "U$4") (pin "1") (pinfunction "C1_1") (pintype "bidirectional"))
      (node (ref "U$4") (pin "10") (pinfunction "C10_10") (pintype "bidirectional"))
      (node (ref "U$4") (pin "2") (pinfunction "C2_2") (pintype "bidirectional"))
      (node (ref "U$4") (pin "27") (pinfunction "C27_27") (pintype "bidirectional"))
      (node (ref "U$4") (pin "28") (pinfunction "C28_28") (pintype "bidirectional"))
      (node (ref "U$4") (pin "39") (pinfunction "C39_39") (pintype "bidirectional"))
      (node (ref "U$4") (pin "40") (pinfunction "C40_40") (pintype "bidirectional"))
      (node (ref "U$4") (pin "47") (pinfunction "C47_47") (pintype "bidirectional"))
      (node (ref "U$4") (pin "48") (pinfunction "C48_48") (pintype "bidirectional"))
      (node (ref "U$4") (pin "7") (pinfunction "C7_7") (pintype "bidirectional"))
      (node (ref "U$4") (pin "8") (pinfunction "C8_8") (pintype "bidirectional"))
      (node (ref "U$4") (pin "9") (pinfunction "C9_9") (pintype "bidirectional"))
      (node (ref "U$6") (pin "-") (pinfunction "-_-") (pintype "passive"))
      (node (ref "U1") (pin "4") (pinfunction "GND_4") (pintype "passive"))
    )
    (net (code "96") (name "Net-(ADC_TEMP_1-AS)") (class "Default")
      (node (ref "ADC_TEMP_1") (pin "15") (pinfunction "AS_15") (pintype "bidirectional"))
      (node (ref "R3") (pin "2") (pinfunction "2_2") (pintype "passive"))
    )
    (net (code "97") (name "Net-(ADC_TEMP_1-REF_IN)") (class "Default")
      (node (ref "ADC_TEMP_1") (pin "6") (pinfunction "REF_IN_6") (pintype "bidirectional"))
      (node (ref "ADC_TEMP_2") (pin "6") (pinfunction "REF_IN_6") (pintype "bidirectional"))
      (node (ref "C3") (pin "1") (pinfunction "1_1") (pintype "passive"))
      (node (ref "C4") (pin "2") (pinfunction "2_2") (pintype "passive"))
      (node (ref "D1") (pin "C") (pinfunction "C_C") (pintype "passive"))
      (node (ref "R6") (pin "1") (pinfunction "1_1") (pintype "passive"))
    )
    (net (code "98") (name "Net-(U$6-+)") (class "Default")
      (node (ref "U$6") (pin "+$1") (pinfunction "+_+$1") (pintype "passive"))
      (node (ref "U$6") (pin "+$2") (pinfunction "+1_+$2") (pintype "passive"))
      (node (ref "U1") (pin "3") (pinfunction "VBAT_3") (pintype "power_in"))
    )
    (net (code "99") (name "Net-(U1-SQW{slash}OUT)") (class "Default")
      (node (ref "R2") (pin "1") (pinfunction "1_1") (pintype "passive"))
      (node (ref "U1") (pin "8") (pinfunction "SQW/OUT_8") (pintype "output"))
    )
    (net (code "100") (name "Net-(U1-X1)") (class "Default")
      (node (ref "Q1") (pin "1") (pinfunction "1_1") (pintype "passive"))
      (node (ref "U1") (pin "1") (pinfunction "X1_1") (pintype "input"))
    )
    (net (code "101") (name "Net-(U1-X2)") (class "Default")
      (node (ref "Q1") (pin "2") (pinfunction "2_2") (pintype "passive"))
      (node (ref "U1") (pin "2") (pinfunction "X2_2") (pintype "output"))
    )
    (net (code "102") (name "unconnected-(ADC_TEMP_1-ALERT{slash}BUSY-Pad17)") (class "Default")
      (node (ref "ADC_TEMP_1") (pin "17") (pinfunction "ALERT/BUSY_17") (pintype "bidirectional"))
    )
    (net (code "103") (name "unconnected-(ADC_TEMP_2-ALERT{slash}BUSY-Pad17)") (class "Default")
      (node (ref "ADC_TEMP_2") (pin "17") (pinfunction "ALERT/BUSY_17") (pintype "bidirectional"))
    )
    (net (code "104") (name "unconnected-(H1-Pad2)") (class "Default")
      (node (ref "H1") (pin "2") (pinfunction "2_2") (pintype "bidirectional"))
    )
    (net (code "105") (name "unconnected-(H2-Pad21)") (class "Default")
      (node (ref "H2") (pin "21") (pinfunction "21_21") (pintype "bidirectional"))
    )
    (net (code "106") (name "unconnected-(H2-Pad23)") (class "Default")
      (node (ref "H2") (pin "23") (pinfunction "23_23") (pintype "bidirectional"))
    )
    (net (code "107") (name "unconnected-(H2-Pad25)") (class "Default")
      (node (ref "H2") (pin "25") (pinfunction "25_25") (pintype "bidirectional"))
    )
    (net (code "108") (name "unconnected-(H2-Pad35)") (class "Default")
      (node (ref "H2") (pin "35") (pinfunction "35_35") (pintype "bidirectional"))
    )
    (net (code "109") (name "unconnected-(H2-Pad37)") (class "Default")
      (node (ref "H2") (pin "37") (pinfunction "37_37") (pintype "bidirectional"))
    )
  )
)
